# oLoRa-part-Coprocessor.net
KiCad netlist of a schematic drawn in EasyEDA
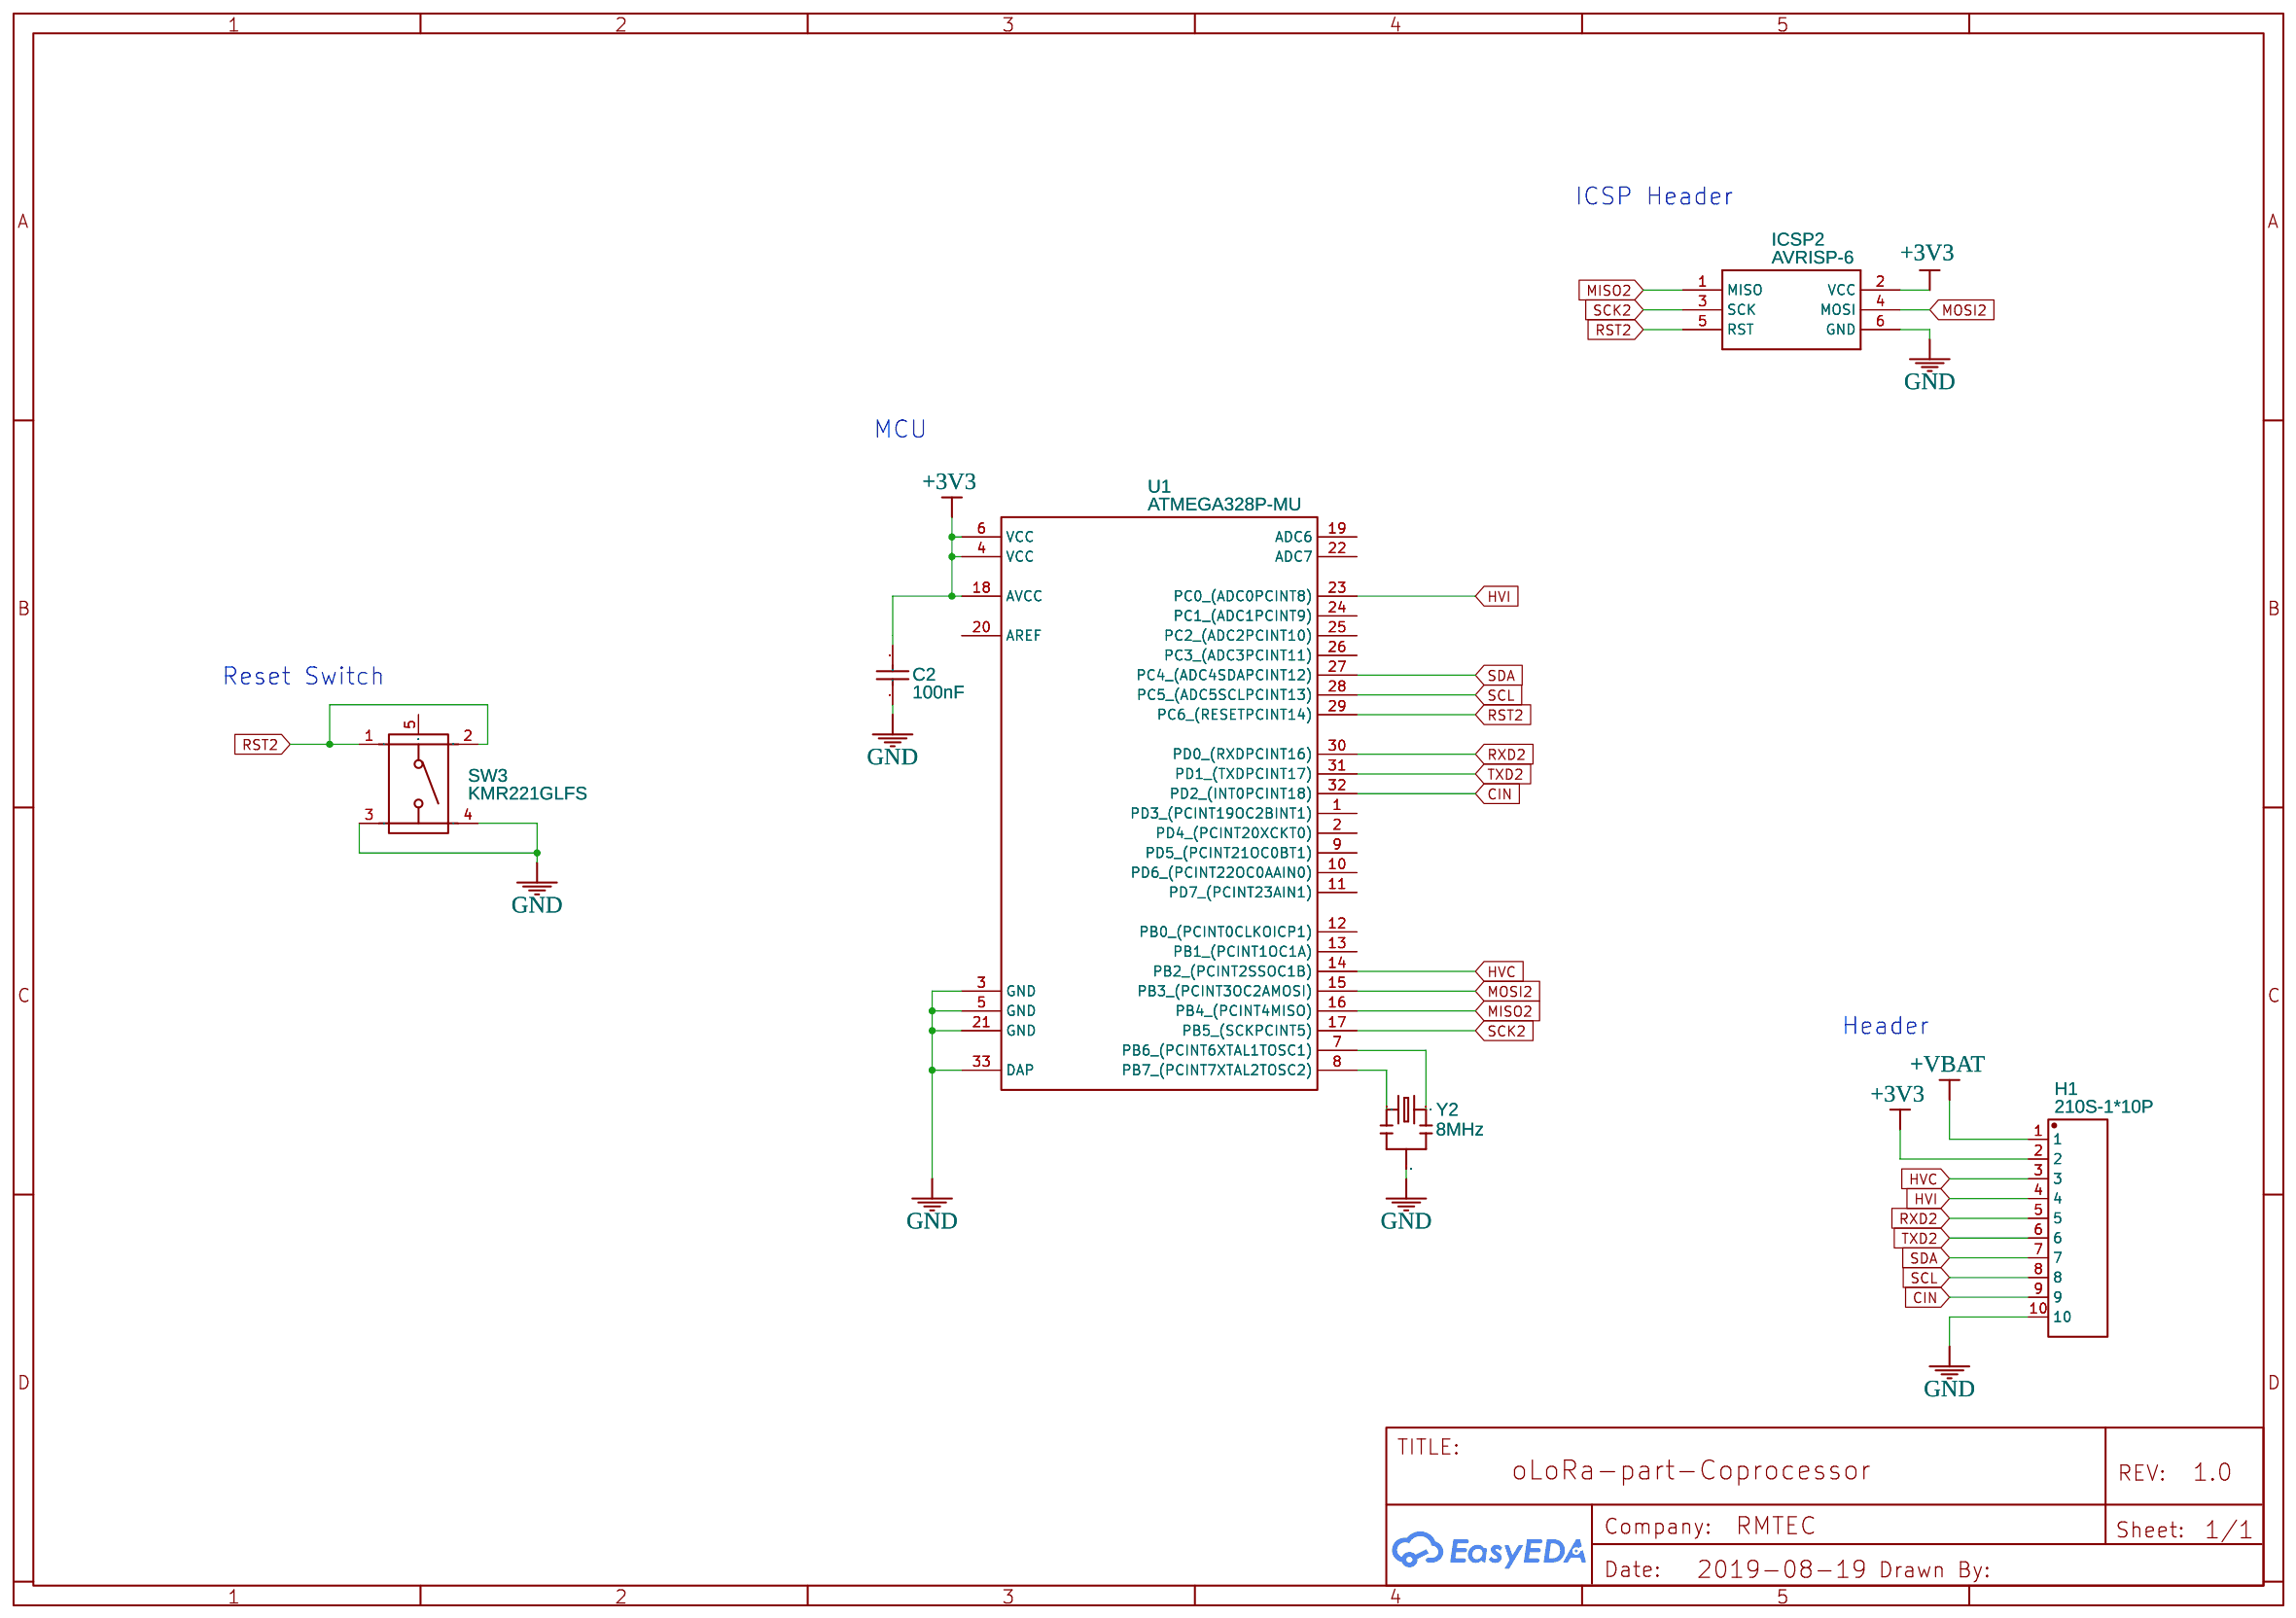
[diagram p0: schematic sheet]

(export (version "E")
  (design (tool "Eeschema 10.0.6"))
  (components
    (comp (ref "C2")
      (value "100nF")
      (fields
        (field (name "BOM_Manufacturer Part") "0603B104K500NT")
        (field (name "BOM_Supplier Part") "C30926")
      )
      (libsource (lib "") (part "0603B104K500NT"))
    )
    (comp (ref "H1")
      (value "210S-1*10P")
      (fields
        (field (name "BOM_Manufacturer Part") "210S-1*10P L=11.6MMGold-plated black")
        (field (name "BOM_Supplier Part") "C124372")
      )
      (libsource (lib "") (part "Unknown_1040_615"))
    )
    (comp (ref "ICSP2")
      (value "AVRISP-6")
      (fields (field (name "BOM_Manufacturer Part") "?"))
      (libsource (lib "") (part "Unknown_895_150"))
    )
    (comp (ref "SW3")
      (value "KMR221GLFS")
      (fields (field (name "BOM_Supplier Part") "C72443"))
      (libsource (lib "") (part "Unknown_205_385"))
    )
    (comp (ref "U1")
      (value "ATMEGA328P-MU")
      (fields (field (name "BOM_Supplier Part") "C38896"))
      (libsource (lib "") (part "Unknown_580_400"))
    )
    (comp (ref "Y2")
      (value "8MHz")
      (fields (field (name "BOM_Manufacturer Part") "CSTCE8M00G55-R0"))
      (libsource (lib "") (part "Unknown_705_555"))
    )
  )
  (nets
    (net (code "1") (name "+3V3") (class "Default")
      (node (ref "C2") (pin "1") (pinfunction "1_1") (pintype "input"))
      (node (ref "H1") (pin "2") (pinfunction "2_2") (pintype "unspecified"))
      (node (ref "ICSP2") (pin "2") (pinfunction "VCC_2") (pintype "passive"))
      (node (ref "U1") (pin "18") (pinfunction "AVCC_18") (pintype "passive"))
      (node (ref "U1") (pin "4") (pinfunction "VCC_4") (pintype "passive"))
      (node (ref "U1") (pin "6") (pinfunction "VCC_6") (pintype "passive"))
    )
    (net (code "2") (name "+VBAT") (class "Default")
      (node (ref "H1") (pin "1") (pinfunction "1_1") (pintype "unspecified"))
    )
    (net (code "3") (name "CIN") (class "Default")
      (node (ref "H1") (pin "9") (pinfunction "9_9") (pintype "unspecified"))
      (node (ref "U1") (pin "32") (pinfunction "PD2_(INT0PCINT18)_32") (pintype "bidirectional"))
    )
    (net (code "4") (name "GND") (class "Default")
      (node (ref "C2") (pin "2") (pinfunction "2_2") (pintype "input"))
      (node (ref "H1") (pin "10") (pinfunction "10_10") (pintype "unspecified"))
      (node (ref "ICSP2") (pin "6") (pinfunction "GND_6") (pintype "passive"))
      (node (ref "SW3") (pin "3") (pinfunction "3_3") (pintype "unspecified"))
      (node (ref "SW3") (pin "4") (pinfunction "4_4") (pintype "unspecified"))
      (node (ref "U1") (pin "21") (pinfunction "GND_21") (pintype "passive"))
      (node (ref "U1") (pin "3") (pinfunction "GND_3") (pintype "passive"))
      (node (ref "U1") (pin "33") (pinfunction "DAP_33") (pintype "passive"))
      (node (ref "U1") (pin "5") (pinfunction "GND_5") (pintype "passive"))
      (node (ref "Y2") (pin "2") (pinfunction "2_2") (pintype "unspecified"))
    )
    (net (code "5") (name "HVC") (class "Default")
      (node (ref "H1") (pin "3") (pinfunction "3_3") (pintype "unspecified"))
      (node (ref "U1") (pin "14") (pinfunction "PB2_(PCINT2SSOC1B)_14") (pintype "bidirectional"))
    )
    (net (code "6") (name "HVI") (class "Default")
      (node (ref "H1") (pin "4") (pinfunction "4_4") (pintype "unspecified"))
      (node (ref "U1") (pin "23") (pinfunction "PC0_(ADC0PCINT8)_23") (pintype "bidirectional"))
    )
    (net (code "7") (name "MISO2") (class "Default")
      (node (ref "ICSP2") (pin "1") (pinfunction "MISO_1") (pintype "input"))
      (node (ref "U1") (pin "16") (pinfunction "PB4_(PCINT4MISO)_16") (pintype "bidirectional"))
    )
    (net (code "8") (name "MOSI2") (class "Default")
      (node (ref "ICSP2") (pin "4") (pinfunction "MOSI_4") (pintype "output"))
      (node (ref "U1") (pin "15") (pinfunction "PB3_(PCINT3OC2AMOSI)_15") (pintype "bidirectional"))
    )
    (net (code "9") (name "Net-(U1-PB6_(PCINT6XTAL1TOSC1))") (class "Default")
      (node (ref "U1") (pin "7") (pinfunction "PB6_(PCINT6XTAL1TOSC1)_7") (pintype "bidirectional"))
      (node (ref "Y2") (pin "3") (pinfunction "3_3") (pintype "unspecified"))
    )
    (net (code "10") (name "Net-(U1-PB7_(PCINT7XTAL2TOSC2))") (class "Default")
      (node (ref "U1") (pin "8") (pinfunction "PB7_(PCINT7XTAL2TOSC2)_8") (pintype "bidirectional"))
      (node (ref "Y2") (pin "1") (pinfunction "1_1") (pintype "unspecified"))
    )
    (net (code "11") (name "RST2") (class "Default")
      (node (ref "ICSP2") (pin "5") (pinfunction "RST_5") (pintype "output"))
      (node (ref "SW3") (pin "1") (pinfunction "1_1") (pintype "unspecified"))
      (node (ref "SW3") (pin "2") (pinfunction "2_2") (pintype "unspecified"))
      (node (ref "U1") (pin "29") (pinfunction "PC6_(RESETPCINT14)_29") (pintype "bidirectional"))
    )
    (net (code "12") (name "RXD2") (class "Default")
      (node (ref "H1") (pin "5") (pinfunction "5_5") (pintype "unspecified"))
      (node (ref "U1") (pin "30") (pinfunction "PD0_(RXDPCINT16)_30") (pintype "bidirectional"))
    )
    (net (code "13") (name "SCK2") (class "Default")
      (node (ref "ICSP2") (pin "3") (pinfunction "SCK_3") (pintype "output"))
      (node (ref "U1") (pin "17") (pinfunction "PB5_(SCKPCINT5)_17") (pintype "bidirectional"))
    )
    (net (code "14") (name "SCL") (class "Default")
      (node (ref "H1") (pin "8") (pinfunction "8_8") (pintype "unspecified"))
      (node (ref "U1") (pin "28") (pinfunction "PC5_(ADC5SCLPCINT13)_28") (pintype "bidirectional"))
    )
    (net (code "15") (name "SDA") (class "Default")
      (node (ref "H1") (pin "7") (pinfunction "7_7") (pintype "unspecified"))
      (node (ref "U1") (pin "27") (pinfunction "PC4_(ADC4SDAPCINT12)_27") (pintype "bidirectional"))
    )
    (net (code "16") (name "TXD2") (class "Default")
      (node (ref "H1") (pin "6") (pinfunction "6_6") (pintype "unspecified"))
      (node (ref "U1") (pin "31") (pinfunction "PD1_(TXDPCINT17)_31") (pintype "bidirectional"))
    )
    (net (code "17") (name "unconnected-(SW3-Pad5)") (class "Default")
      (node (ref "SW3") (pin "5") (pinfunction "5_5") (pintype "unspecified"))
    )
    (net (code "18") (name "unconnected-(U1-ADC6-Pad19)") (class "Default")
      (node (ref "U1") (pin "19") (pinfunction "ADC6_19") (pintype "unspecified"))
    )
    (net (code "19") (name "unconnected-(U1-ADC7-Pad22)") (class "Default")
      (node (ref "U1") (pin "22") (pinfunction "ADC7_22") (pintype "unspecified"))
    )
    (net (code "20") (name "unconnected-(U1-AREF-Pad20)") (class "Default")
      (node (ref "U1") (pin "20") (pinfunction "AREF_20") (pintype "unspecified"))
    )
    (net (code "21") (name "unconnected-(U1-PB0_(PCINT0CLKOICP1)-Pad12)") (class "Default")
      (node (ref "U1") (pin "12") (pinfunction "PB0_(PCINT0CLKOICP1)_12") (pintype "bidirectional"))
    )
    (net (code "22") (name "unconnected-(U1-PB1_(PCINT1OC1A)-Pad13)") (class "Default")
      (node (ref "U1") (pin "13") (pinfunction "PB1_(PCINT1OC1A)_13") (pintype "bidirectional"))
    )
    (net (code "23") (name "unconnected-(U1-PC1_(ADC1PCINT9)-Pad24)") (class "Default")
      (node (ref "U1") (pin "24") (pinfunction "PC1_(ADC1PCINT9)_24") (pintype "bidirectional"))
    )
    (net (code "24") (name "unconnected-(U1-PC2_(ADC2PCINT10)-Pad25)") (class "Default")
      (node (ref "U1") (pin "25") (pinfunction "PC2_(ADC2PCINT10)_25") (pintype "bidirectional"))
    )
    (net (code "25") (name "unconnected-(U1-PC3_(ADC3PCINT11)-Pad26)") (class "Default")
      (node (ref "U1") (pin "26") (pinfunction "PC3_(ADC3PCINT11)_26") (pintype "bidirectional"))
    )
    (net (code "26") (name "unconnected-(U1-PD3_(PCINT19OC2BINT1)-Pad1)") (class "Default")
      (node (ref "U1") (pin "1") (pinfunction "PD3_(PCINT19OC2BINT1)_1") (pintype "bidirectional"))
    )
    (net (code "27") (name "unconnected-(U1-PD4_(PCINT20XCKT0)-Pad2)") (class "Default")
      (node (ref "U1") (pin "2") (pinfunction "PD4_(PCINT20XCKT0)_2") (pintype "bidirectional"))
    )
    (net (code "28") (name "unconnected-(U1-PD5_(PCINT21OC0BT1)-Pad9)") (class "Default")
      (node (ref "U1") (pin "9") (pinfunction "PD5_(PCINT21OC0BT1)_9") (pintype "bidirectional"))
    )
    (net (code "29") (name "unconnected-(U1-PD6_(PCINT22OC0AAIN0)-Pad10)") (class "Default")
      (node (ref "U1") (pin "10") (pinfunction "PD6_(PCINT22OC0AAIN0)_10") (pintype "bidirectional"))
    )
    (net (code "30") (name "unconnected-(U1-PD7_(PCINT23AIN1)-Pad11)") (class "Default")
      (node (ref "U1") (pin "11") (pinfunction "PD7_(PCINT23AIN1)_11") (pintype "bidirectional"))
    )
  )
)
